# Sheet1.net
KiCad netlist of a schematic drawn in Altium Designer
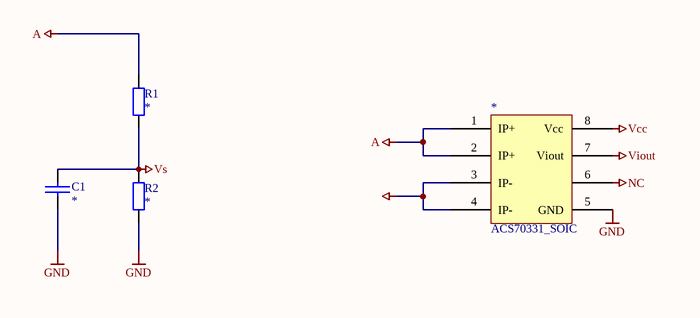
[diagram p0: Sheet1.SchDoc]

(export (version "E")
  (design (tool "Eeschema 10.0.6"))
  (components
    (comp (ref "*")
      (value "ACS70331_SOIC")
      (footprint "ACS70331")
      (libsource (lib "SumWkshop") (part "ACS70331_SOIC"))
    )
    (comp (ref "C1")
      (value "*")
      (footprint "0805 CAP")
      (description "SMT ceramic capacitor 0805 size")
      (libsource (lib "EE209_Library (1)") (part "CerCap_SMT_0805"))
    )
    (comp (ref "R1")
      (value "*")
      (footprint "0805 RES")
      (description "0805 resistor")
      (fields (field (name "PUBLISHER") "Altium Limited"))
      (libsource (lib "EE209_Library (1)") (part "Res_SMT_0805"))
    )
    (comp (ref "R2")
      (value "*")
      (footprint "0805 RES")
      (description "0805 resistor")
      (fields (field (name "PUBLISHER") "Altium Limited"))
      (libsource (lib "EE209_Library (1)") (part "Res_SMT_0805"))
    )
  )
  (nets
    (net (code "1") (name "<NO NET>") (class "Default")
      (node (ref "*") (pin "3") (pinfunction "IP-_3") (pintype "passive"))
      (node (ref "*") (pin "4") (pinfunction "IP-_4") (pintype "passive"))
    )
    (net (code "2") (name "A") (class "Default")
      (node (ref "*") (pin "1") (pinfunction "IP+_1") (pintype "passive"))
      (node (ref "*") (pin "2") (pinfunction "IP+_2") (pintype "passive"))
      (node (ref "R1") (pin "2") (pinfunction "2_2") (pintype "passive"))
    )
    (net (code "3") (name "GND") (class "Default")
      (node (ref "*") (pin "5") (pinfunction "GND_5") (pintype "passive"))
      (node (ref "C1") (pin "2") (pinfunction "2_2") (pintype "passive"))
      (node (ref "R2") (pin "1") (pinfunction "1_1") (pintype "passive"))
    )
    (net (code "4") (name "NC") (class "Default") (node (ref "*") (pin "6") (pintype "passive")))
    (net (code "5") (name "Vcc") (class "Default")
      (node (ref "*") (pin "8") (pinfunction "Vcc_8") (pintype "passive"))
    )
    (net (code "6") (name "Viout") (class "Default")
      (node (ref "*") (pin "7") (pinfunction "Viout_7") (pintype "passive"))
    )
    (net (code "7") (name "Vs") (class "Default")
      (node (ref "C1") (pin "1") (pinfunction "1_1") (pintype "passive"))
      (node (ref "R1") (pin "1") (pinfunction "1_1") (pintype "passive"))
      (node (ref "R2") (pin "2") (pinfunction "2_2") (pintype "passive"))
    )
  )
)
